# SCH-microphone-module-2025-06-26.net
KiCad netlist of a schematic drawn in Altium Designer
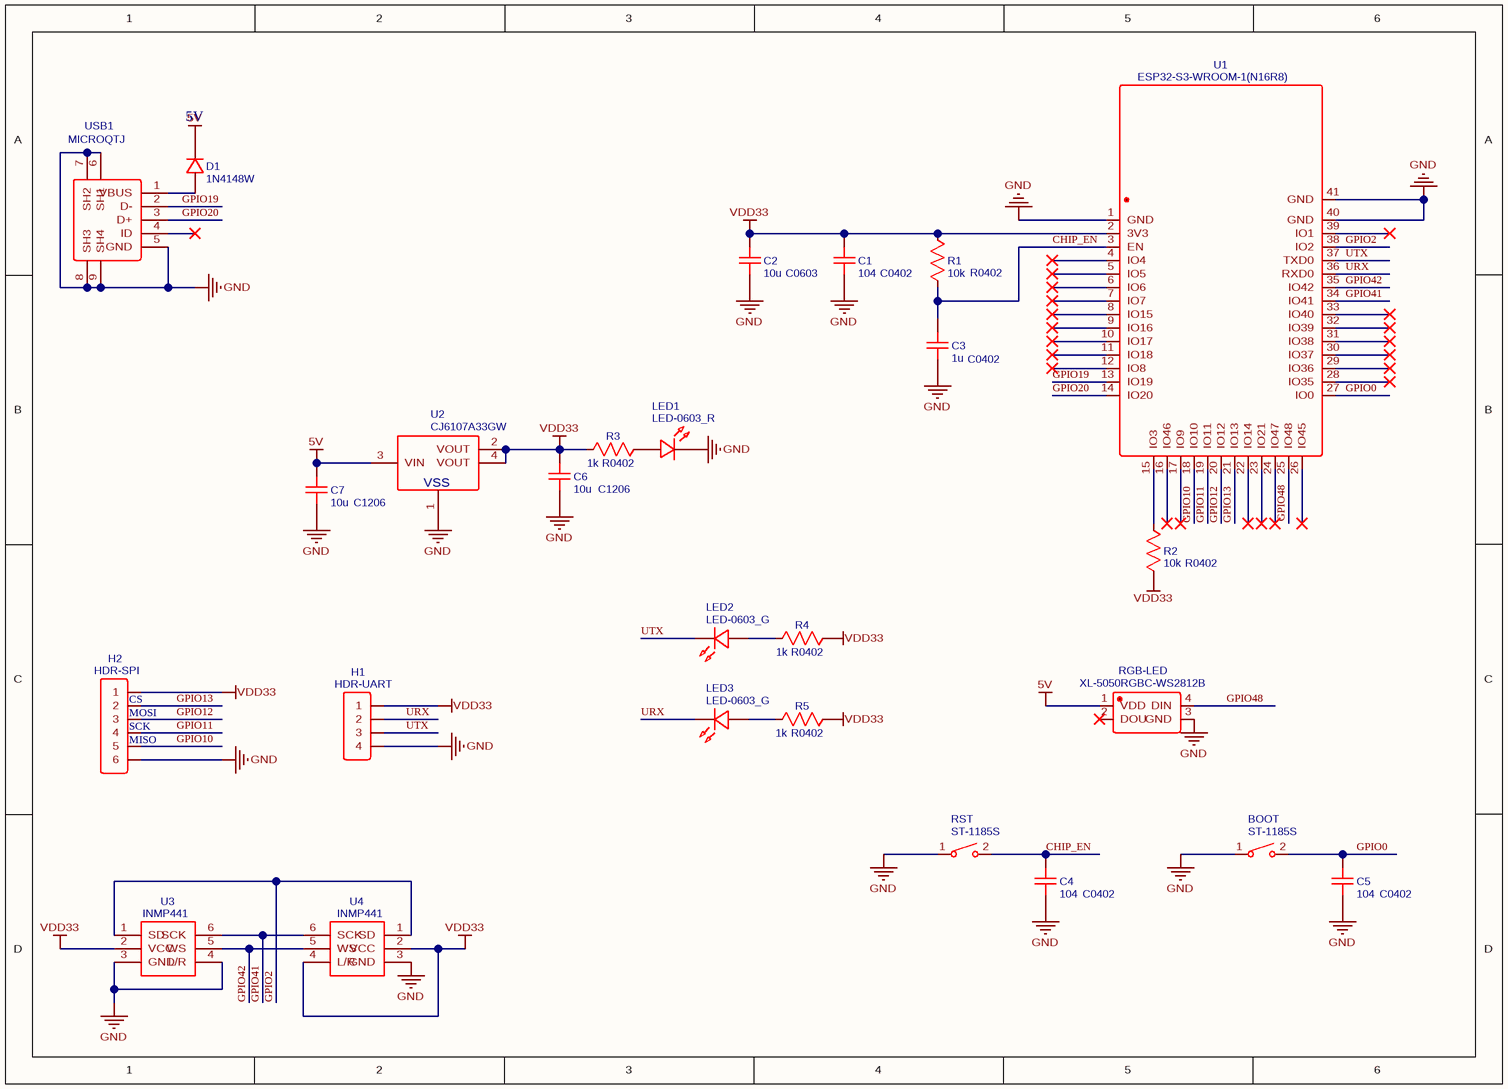
[diagram p0: SCH-microphone-module-2025-06-26.schdoc]

(export (version "E")
  (design (tool "Eeschema 10.0.6"))
  (components
    (comp (ref "BOOT")
      (value "ST-1185S")
      (fields (field (name "MANUFACTURER") "RISHENG(日昇)") (field (name "CONTRIBUTOR") "LCSC"))
      (libsource (lib "altium-import") (part "root_0_ST-1185S_"))
    )
    (comp (ref "C1")
      (value "104")
      (fields (field (name "CONTRIBUTOR") "LCEDA_Lib"))
      (libsource (lib "altium-import") (part "root_1_104_"))
    )
    (comp (ref "C2")
      (value "10u")
      (fields (field (name "CONTRIBUTOR") "LCEDA_Lib"))
      (libsource (lib "altium-import") (part "root_1_10u_"))
    )
    (comp (ref "C3")
      (value "1u")
      (fields (field (name "CONTRIBUTOR") "LCEDA_Lib"))
      (libsource (lib "altium-import") (part "root_1_1u_"))
    )
    (comp (ref "C4")
      (value "104")
      (fields (field (name "CONTRIBUTOR") "LCEDA_Lib"))
      (libsource (lib "altium-import") (part "root_1_104_"))
    )
    (comp (ref "C5")
      (value "104")
      (fields (field (name "CONTRIBUTOR") "LCEDA_Lib"))
      (libsource (lib "altium-import") (part "root_1_104_"))
    )
    (comp (ref "C6")
      (value "10u")
      (fields (field (name "CONTRIBUTOR") "LCEDA_Lib"))
      (libsource (lib "altium-import") (part "root_1_10u_"))
    )
    (comp (ref "C7")
      (value "10u")
      (fields (field (name "CONTRIBUTOR") "LCEDA_Lib"))
      (libsource (lib "altium-import") (part "root_1_10u_"))
    )
    (comp (ref "D1")
      (value "1N4148W")
      (fields (field (name "MANUFACTURER") "Tak Cheong") (field (name "CONTRIBUTOR") "LCEDA_Lib"))
      (libsource (lib "altium-import") (part "root_1_1N4148W_"))
    )
    (comp (ref "H1")
      (value "HDR-UART")
      (fields (field (name "CONTRIBUTOR") "LCEDA_Lib"))
      (libsource (lib "altium-import") (part "root_0_HDR-UART_"))
    )
    (comp (ref "H2")
      (value "HDR-SPI")
      (fields (field (name "CONTRIBUTOR") "LCEDA_Lib"))
      (libsource (lib "altium-import") (part "root_0_HDR-SPI_"))
    )
    (comp (ref "LED1")
      (value "LED-0603_R")
      (fields
        (field (name "MANUFACTURER") "EVERLIGHT(台湾亿光)")
        (field (name "MANUFACTURER PART") "19-217/R6C-AL1M2VY/3T")
        (field (name "CONTRIBUTOR") "LCEDA_01")
      )
      (libsource (lib "altium-import") (part "root_0_LED-0603_R_"))
    )
    (comp (ref "LED2")
      (value "LED-0603_G")
      (fields
        (field (name "MANUFACTURER") "EVERLIGHT(台湾亿光)")
        (field (name "MANUFACTURER PART") "19-217/GHC-YR1S2/3T")
        (field (name "CONTRIBUTOR") "LCEDA_Lib")
      )
      (libsource (lib "altium-import") (part "root_2_LED-0603_G_"))
    )
    (comp (ref "LED3")
      (value "LED-0603_G")
      (fields
        (field (name "MANUFACTURER") "EVERLIGHT(台湾亿光)")
        (field (name "MANUFACTURER PART") "19-217/GHC-YR1S2/3T")
        (field (name "CONTRIBUTOR") "LCEDA_Lib")
      )
      (libsource (lib "altium-import") (part "root_2_LED-0603_G_"))
    )
    (comp (ref "R1")
      (value "10k")
      (fields (field (name "CONTRIBUTOR") "LCEDA_Lib"))
      (libsource (lib "altium-import") (part "root_1_10k_"))
    )
    (comp (ref "R2")
      (value "10k")
      (fields (field (name "CONTRIBUTOR") "LCEDA_Lib"))
      (libsource (lib "altium-import") (part "root_3_10k_"))
    )
    (comp (ref "R3")
      (value "1k")
      (fields (field (name "CONTRIBUTOR") "LCEDA_Lib"))
      (libsource (lib "altium-import") (part "root_0_1k_"))
    )
    (comp (ref "R4")
      (value "1k")
      (fields (field (name "CONTRIBUTOR") "LCEDA_Lib"))
      (libsource (lib "altium-import") (part "root_0_1k_"))
    )
    (comp (ref "R5")
      (value "1k")
      (fields (field (name "CONTRIBUTOR") "LCEDA_Lib"))
      (libsource (lib "altium-import") (part "root_0_1k_"))
    )
    (comp (ref "RGB-LED")
      (value "XL-5050RGBC-WS2812B")
      (fields (field (name "MANUFACTURER") "XINGLIGHT(成兴光)") (field (name "CONTRIBUTOR") "LCSC"))
      (libsource (lib "altium-import") (part "root_0_XL-5050RGBC-WS2812B_"))
    )
    (comp (ref "RST")
      (value "ST-1185S")
      (fields (field (name "MANUFACTURER") "RISHENG(日昇)") (field (name "CONTRIBUTOR") "LCSC"))
      (libsource (lib "altium-import") (part "root_0_ST-1185S_"))
    )
    (comp (ref "U1")
      (value "ESP32-S3-WROOM-1(N16R8)")
      (fields
        (field (name "MANUFACTURER") "ESPRESSIF(乐鑫)")
        (field (name "MANUFACTURER PART") "ESP32-S3-WROOM-1-N16R8")
        (field (name "CONTRIBUTOR") "lcsc")
      )
      (libsource (lib "altium-import") (part "root_0_ESP32-S3-WROOM-1(N16R8)_"))
    )
    (comp (ref "U2")
      (value "CJ6107A33GW")
      (fields (field (name "MANUFACTURER") "CJ(江苏长电/长晶)") (field (name "CONTRIBUTOR") "LCSC"))
      (libsource (lib "altium-import") (part "root_0_CJ6107A33GW_"))
    )
    (comp (ref "U3")
      (value "INMP441")
      (fields (field (name "CONTRIBUTOR") "venuraju"))
      (libsource (lib "") (part "root_0_INMP441__1"))
    )
    (comp (ref "U4")
      (value "INMP441")
      (fields (field (name "CONTRIBUTOR") "venuraju"))
      (libsource (lib "altium-import") (part "root_0_INMP441_"))
    )
    (comp (ref "USB1")
      (value "MICROQTJ")
      (fields
        (field (name "MANUFACTURER") "SHOU HAN(首韩)")
        (field (name "MANUFACTURER PART") "MicroQTJ")
        (field (name "CONTRIBUTOR") "LCSC")
      )
      (libsource (lib "altium-import") (part "root_0_MICROQTJ_"))
    )
  )
  (nets
    (net (code "1") (name "/CHIP_EN") (class "Default")
      (node (ref "C3") (pin "2") (pinfunction "2_2") (pintype "passive"))
      (node (ref "C4") (pin "2") (pinfunction "2_2") (pintype "passive"))
      (node (ref "R1") (pin "1") (pinfunction "1_1") (pintype "passive"))
      (node (ref "RST") (pin "2") (pinfunction "2_2") (pintype "passive"))
      (node (ref "U1") (pin "3") (pinfunction "EN_3") (pintype "passive"))
    )
    (net (code "2") (name "/GPIO0") (class "Default")
      (node (ref "BOOT") (pin "2") (pinfunction "2_2") (pintype "passive"))
      (node (ref "C5") (pin "2") (pinfunction "2_2") (pintype "passive"))
      (node (ref "U1") (pin "27") (pinfunction "IO0_27") (pintype "passive"))
    )
    (net (code "3") (name "/GPIO2") (class "Default")
      (node (ref "U1") (pin "38") (pinfunction "IO2_38") (pintype "passive"))
      (node (ref "U3") (pin "1") (pinfunction "SD_1") (pintype "passive"))
      (node (ref "U4") (pin "1") (pinfunction "SD_1") (pintype "passive"))
    )
    (net (code "4") (name "/GPIO10") (class "Default")
      (node (ref "H2") (pin "5") (pinfunction "5_5") (pintype "passive"))
      (node (ref "U1") (pin "18") (pinfunction "IO10_18") (pintype "passive"))
    )
    (net (code "5") (name "/GPIO11") (class "Default")
      (node (ref "H2") (pin "4") (pinfunction "4_4") (pintype "passive"))
      (node (ref "U1") (pin "19") (pinfunction "IO11_19") (pintype "passive"))
    )
    (net (code "6") (name "/GPIO12") (class "Default")
      (node (ref "H2") (pin "3") (pinfunction "3_3") (pintype "passive"))
      (node (ref "U1") (pin "20") (pinfunction "IO12_20") (pintype "passive"))
    )
    (net (code "7") (name "/GPIO13") (class "Default")
      (node (ref "H2") (pin "2") (pinfunction "2_2") (pintype "passive"))
      (node (ref "U1") (pin "21") (pinfunction "IO13_21") (pintype "passive"))
    )
    (net (code "8") (name "/GPIO19") (class "Default")
      (node (ref "U1") (pin "13") (pinfunction "IO19_13") (pintype "passive"))
      (node (ref "USB1") (pin "2") (pinfunction "D-_2") (pintype "passive"))
    )
    (net (code "9") (name "/GPIO20") (class "Default")
      (node (ref "U1") (pin "14") (pinfunction "IO20_14") (pintype "passive"))
      (node (ref "USB1") (pin "3") (pinfunction "D+_3") (pintype "passive"))
    )
    (net (code "10") (name "/GPIO41") (class "Default")
      (node (ref "U1") (pin "34") (pinfunction "IO41_34") (pintype "passive"))
      (node (ref "U3") (pin "6") (pinfunction "SCK_6") (pintype "passive"))
      (node (ref "U4") (pin "6") (pinfunction "SCK_6") (pintype "passive"))
    )
    (net (code "11") (name "/GPIO42") (class "Default")
      (node (ref "U1") (pin "35") (pinfunction "IO42_35") (pintype "passive"))
      (node (ref "U3") (pin "5") (pinfunction "WS_5") (pintype "passive"))
      (node (ref "U4") (pin "5") (pinfunction "WS_5") (pintype "passive"))
    )
    (net (code "12") (name "/GPIO48") (class "Default")
      (node (ref "RGB-LED") (pin "4") (pinfunction "DIN_4") (pintype "passive"))
      (node (ref "U1") (pin "25") (pinfunction "IO48_25") (pintype "passive"))
    )
    (net (code "13") (name "/URX") (class "Default")
      (node (ref "H1") (pin "2") (pinfunction "2_2") (pintype "passive"))
      (node (ref "LED3") (pin "2") (pinfunction "2_2") (pintype "passive"))
      (node (ref "U1") (pin "36") (pinfunction "RXD0_36") (pintype "passive"))
    )
    (net (code "14") (name "/UTX") (class "Default")
      (node (ref "H1") (pin "3") (pinfunction "3_3") (pintype "passive"))
      (node (ref "LED2") (pin "2") (pinfunction "2_2") (pintype "passive"))
      (node (ref "U1") (pin "37") (pinfunction "TXD0_37") (pintype "passive"))
    )
    (net (code "15") (name "5V") (class "Default")
      (node (ref "C7") (pin "2") (pinfunction "2_2") (pintype "passive"))
      (node (ref "D1") (pin "1") (pinfunction "1_1") (pintype "passive"))
      (node (ref "RGB-LED") (pin "1") (pinfunction "VDD_1") (pintype "passive"))
      (node (ref "U2") (pin "3") (pinfunction "VIN_3") (pintype "passive"))
    )
    (net (code "16") (name "GND") (class "Default")
      (node (ref "BOOT") (pin "1") (pinfunction "1_1") (pintype "passive"))
      (node (ref "C1") (pin "1") (pinfunction "1_1") (pintype "passive"))
      (node (ref "C2") (pin "1") (pinfunction "1_1") (pintype "passive"))
      (node (ref "C3") (pin "1") (pinfunction "1_1") (pintype "passive"))
      (node (ref "C4") (pin "1") (pinfunction "1_1") (pintype "passive"))
      (node (ref "C5") (pin "1") (pinfunction "1_1") (pintype "passive"))
      (node (ref "C6") (pin "1") (pinfunction "1_1") (pintype "passive"))
      (node (ref "C7") (pin "1") (pinfunction "1_1") (pintype "passive"))
      (node (ref "H1") (pin "4") (pinfunction "4_4") (pintype "passive"))
      (node (ref "H2") (pin "6") (pinfunction "6_6") (pintype "passive"))
      (node (ref "LED1") (pin "2") (pinfunction "2_2") (pintype "passive"))
      (node (ref "RGB-LED") (pin "3") (pinfunction "GND_3") (pintype "passive"))
      (node (ref "RST") (pin "1") (pinfunction "1_1") (pintype "passive"))
      (node (ref "U1") (pin "1") (pinfunction "GND_1") (pintype "passive"))
      (node (ref "U1") (pin "40") (pinfunction "GND_40") (pintype "passive"))
      (node (ref "U1") (pin "41") (pinfunction "GND_41") (pintype "passive"))
      (node (ref "U2") (pin "1") (pinfunction "VSS_1") (pintype "passive"))
      (node (ref "U3") (pin "3") (pinfunction "GND_3") (pintype "passive"))
      (node (ref "U3") (pin "4") (pinfunction "L/R_4") (pintype "passive"))
      (node (ref "U4") (pin "3") (pinfunction "GND_3") (pintype "passive"))
      (node (ref "USB1") (pin "5") (pinfunction "GND_5") (pintype "passive"))
      (node (ref "USB1") (pin "6") (pinfunction "SH1_6") (pintype "passive"))
      (node (ref "USB1") (pin "7") (pinfunction "SH2_7") (pintype "passive"))
      (node (ref "USB1") (pin "8") (pinfunction "SH3_8") (pintype "passive"))
      (node (ref "USB1") (pin "9") (pinfunction "SH4_9") (pintype "passive"))
    )
    (net (code "17") (name "Net-(LED1-Pad1)") (class "Default")
      (node (ref "LED1") (pin "1") (pinfunction "1_1") (pintype "passive"))
      (node (ref "R3") (pin "2") (pinfunction "2_2") (pintype "passive"))
    )
    (net (code "18") (name "Net-(LED2-Pad1)") (class "Default")
      (node (ref "LED2") (pin "1") (pinfunction "1_1") (pintype "passive"))
      (node (ref "R4") (pin "1") (pinfunction "1_1") (pintype "passive"))
    )
    (net (code "19") (name "Net-(LED3-Pad1)") (class "Default")
      (node (ref "LED3") (pin "1") (pinfunction "1_1") (pintype "passive"))
      (node (ref "R5") (pin "1") (pinfunction "1_1") (pintype "passive"))
    )
    (net (code "20") (name "Net-(U1-IO3)") (class "Default")
      (node (ref "R2") (pin "1") (pinfunction "1_1") (pintype "passive"))
      (node (ref "U1") (pin "15") (pinfunction "IO3_15") (pintype "passive"))
    )
    (net (code "21") (name "Net-(USB1-VBUS)") (class "Default")
      (node (ref "D1") (pin "2") (pinfunction "2_2") (pintype "passive"))
      (node (ref "USB1") (pin "1") (pinfunction "VBUS_1") (pintype "passive"))
    )
    (net (code "22") (name "VDD33") (class "Default")
      (node (ref "C1") (pin "2") (pinfunction "2_2") (pintype "passive"))
      (node (ref "C2") (pin "2") (pinfunction "2_2") (pintype "passive"))
      (node (ref "C6") (pin "2") (pinfunction "2_2") (pintype "passive"))
      (node (ref "H1") (pin "1") (pinfunction "1_1") (pintype "passive"))
      (node (ref "H2") (pin "1") (pinfunction "1_1") (pintype "passive"))
      (node (ref "R1") (pin "2") (pinfunction "2_2") (pintype "passive"))
      (node (ref "R2") (pin "2") (pinfunction "2_2") (pintype "passive"))
      (node (ref "R3") (pin "1") (pinfunction "1_1") (pintype "passive"))
      (node (ref "R4") (pin "2") (pinfunction "2_2") (pintype "passive"))
      (node (ref "R5") (pin "2") (pinfunction "2_2") (pintype "passive"))
      (node (ref "U1") (pin "2") (pinfunction "3V3_2") (pintype "passive"))
      (node (ref "U2") (pin "2") (pinfunction "VOUT_2") (pintype "passive"))
      (node (ref "U2") (pin "4") (pinfunction "VOUT_4") (pintype "passive"))
      (node (ref "U3") (pin "2") (pinfunction "VCC_2") (pintype "passive"))
      (node (ref "U4") (pin "2") (pinfunction "VCC_2") (pintype "passive"))
      (node (ref "U4") (pin "4") (pinfunction "L/R_4") (pintype "passive"))
    )
    (net (code "23") (name "unconnected-(RGB-LED-DOU-Pad2)") (class "Default")
      (node (ref "RGB-LED") (pin "2") (pinfunction "DOU_2") (pintype "passive+no_connect"))
    )
    (net (code "24") (name "unconnected-(U1-IO1-Pad39)") (class "Default")
      (node (ref "U1") (pin "39") (pinfunction "IO1_39") (pintype "passive+no_connect"))
    )
    (net (code "25") (name "unconnected-(U1-IO4-Pad4)") (class "Default")
      (node (ref "U1") (pin "4") (pinfunction "IO4_4") (pintype "passive+no_connect"))
    )
    (net (code "26") (name "unconnected-(U1-IO5-Pad5)") (class "Default")
      (node (ref "U1") (pin "5") (pinfunction "IO5_5") (pintype "passive+no_connect"))
    )
    (net (code "27") (name "unconnected-(U1-IO6-Pad6)") (class "Default")
      (node (ref "U1") (pin "6") (pinfunction "IO6_6") (pintype "passive+no_connect"))
    )
    (net (code "28") (name "unconnected-(U1-IO7-Pad7)") (class "Default")
      (node (ref "U1") (pin "7") (pinfunction "IO7_7") (pintype "passive+no_connect"))
    )
    (net (code "29") (name "unconnected-(U1-IO8-Pad12)") (class "Default")
      (node (ref "U1") (pin "12") (pinfunction "IO8_12") (pintype "passive+no_connect"))
    )
    (net (code "30") (name "unconnected-(U1-IO9-Pad17)") (class "Default")
      (node (ref "U1") (pin "17") (pinfunction "IO9_17") (pintype "passive+no_connect"))
    )
    (net (code "31") (name "unconnected-(U1-IO14-Pad22)") (class "Default")
      (node (ref "U1") (pin "22") (pinfunction "IO14_22") (pintype "passive+no_connect"))
    )
    (net (code "32") (name "unconnected-(U1-IO15-Pad8)") (class "Default")
      (node (ref "U1") (pin "8") (pinfunction "IO15_8") (pintype "passive+no_connect"))
    )
    (net (code "33") (name "unconnected-(U1-IO16-Pad9)") (class "Default")
      (node (ref "U1") (pin "9") (pinfunction "IO16_9") (pintype "passive+no_connect"))
    )
    (net (code "34") (name "unconnected-(U1-IO17-Pad10)") (class "Default")
      (node (ref "U1") (pin "10") (pinfunction "IO17_10") (pintype "passive+no_connect"))
    )
    (net (code "35") (name "unconnected-(U1-IO18-Pad11)") (class "Default")
      (node (ref "U1") (pin "11") (pinfunction "IO18_11") (pintype "passive+no_connect"))
    )
    (net (code "36") (name "unconnected-(U1-IO21-Pad23)") (class "Default")
      (node (ref "U1") (pin "23") (pinfunction "IO21_23") (pintype "passive+no_connect"))
    )
    (net (code "37") (name "unconnected-(U1-IO35-Pad28)") (class "Default")
      (node (ref "U1") (pin "28") (pinfunction "IO35_28") (pintype "passive+no_connect"))
    )
    (net (code "38") (name "unconnected-(U1-IO36-Pad29)") (class "Default")
      (node (ref "U1") (pin "29") (pinfunction "IO36_29") (pintype "passive+no_connect"))
    )
    (net (code "39") (name "unconnected-(U1-IO37-Pad30)") (class "Default")
      (node (ref "U1") (pin "30") (pinfunction "IO37_30") (pintype "passive+no_connect"))
    )
    (net (code "40") (name "unconnected-(U1-IO38-Pad31)") (class "Default")
      (node (ref "U1") (pin "31") (pinfunction "IO38_31") (pintype "passive+no_connect"))
    )
    (net (code "41") (name "unconnected-(U1-IO39-Pad32)") (class "Default")
      (node (ref "U1") (pin "32") (pinfunction "IO39_32") (pintype "passive+no_connect"))
    )
    (net (code "42") (name "unconnected-(U1-IO40-Pad33)") (class "Default")
      (node (ref "U1") (pin "33") (pinfunction "IO40_33") (pintype "passive+no_connect"))
    )
    (net (code "43") (name "unconnected-(U1-IO45-Pad26)") (class "Default")
      (node (ref "U1") (pin "26") (pinfunction "IO45_26") (pintype "passive+no_connect"))
    )
    (net (code "44") (name "unconnected-(U1-IO46-Pad16)") (class "Default")
      (node (ref "U1") (pin "16") (pinfunction "IO46_16") (pintype "passive+no_connect"))
    )
    (net (code "45") (name "unconnected-(U1-IO47-Pad24)") (class "Default")
      (node (ref "U1") (pin "24") (pinfunction "IO47_24") (pintype "passive+no_connect"))
    )
    (net (code "46") (name "unconnected-(USB1-ID-Pad4)") (class "Default")
      (node (ref "USB1") (pin "4") (pinfunction "ID_4") (pintype "passive+no_connect"))
    )
  )
)
